# test.net
KiCad netlist of a schematic drawn in EAGLE
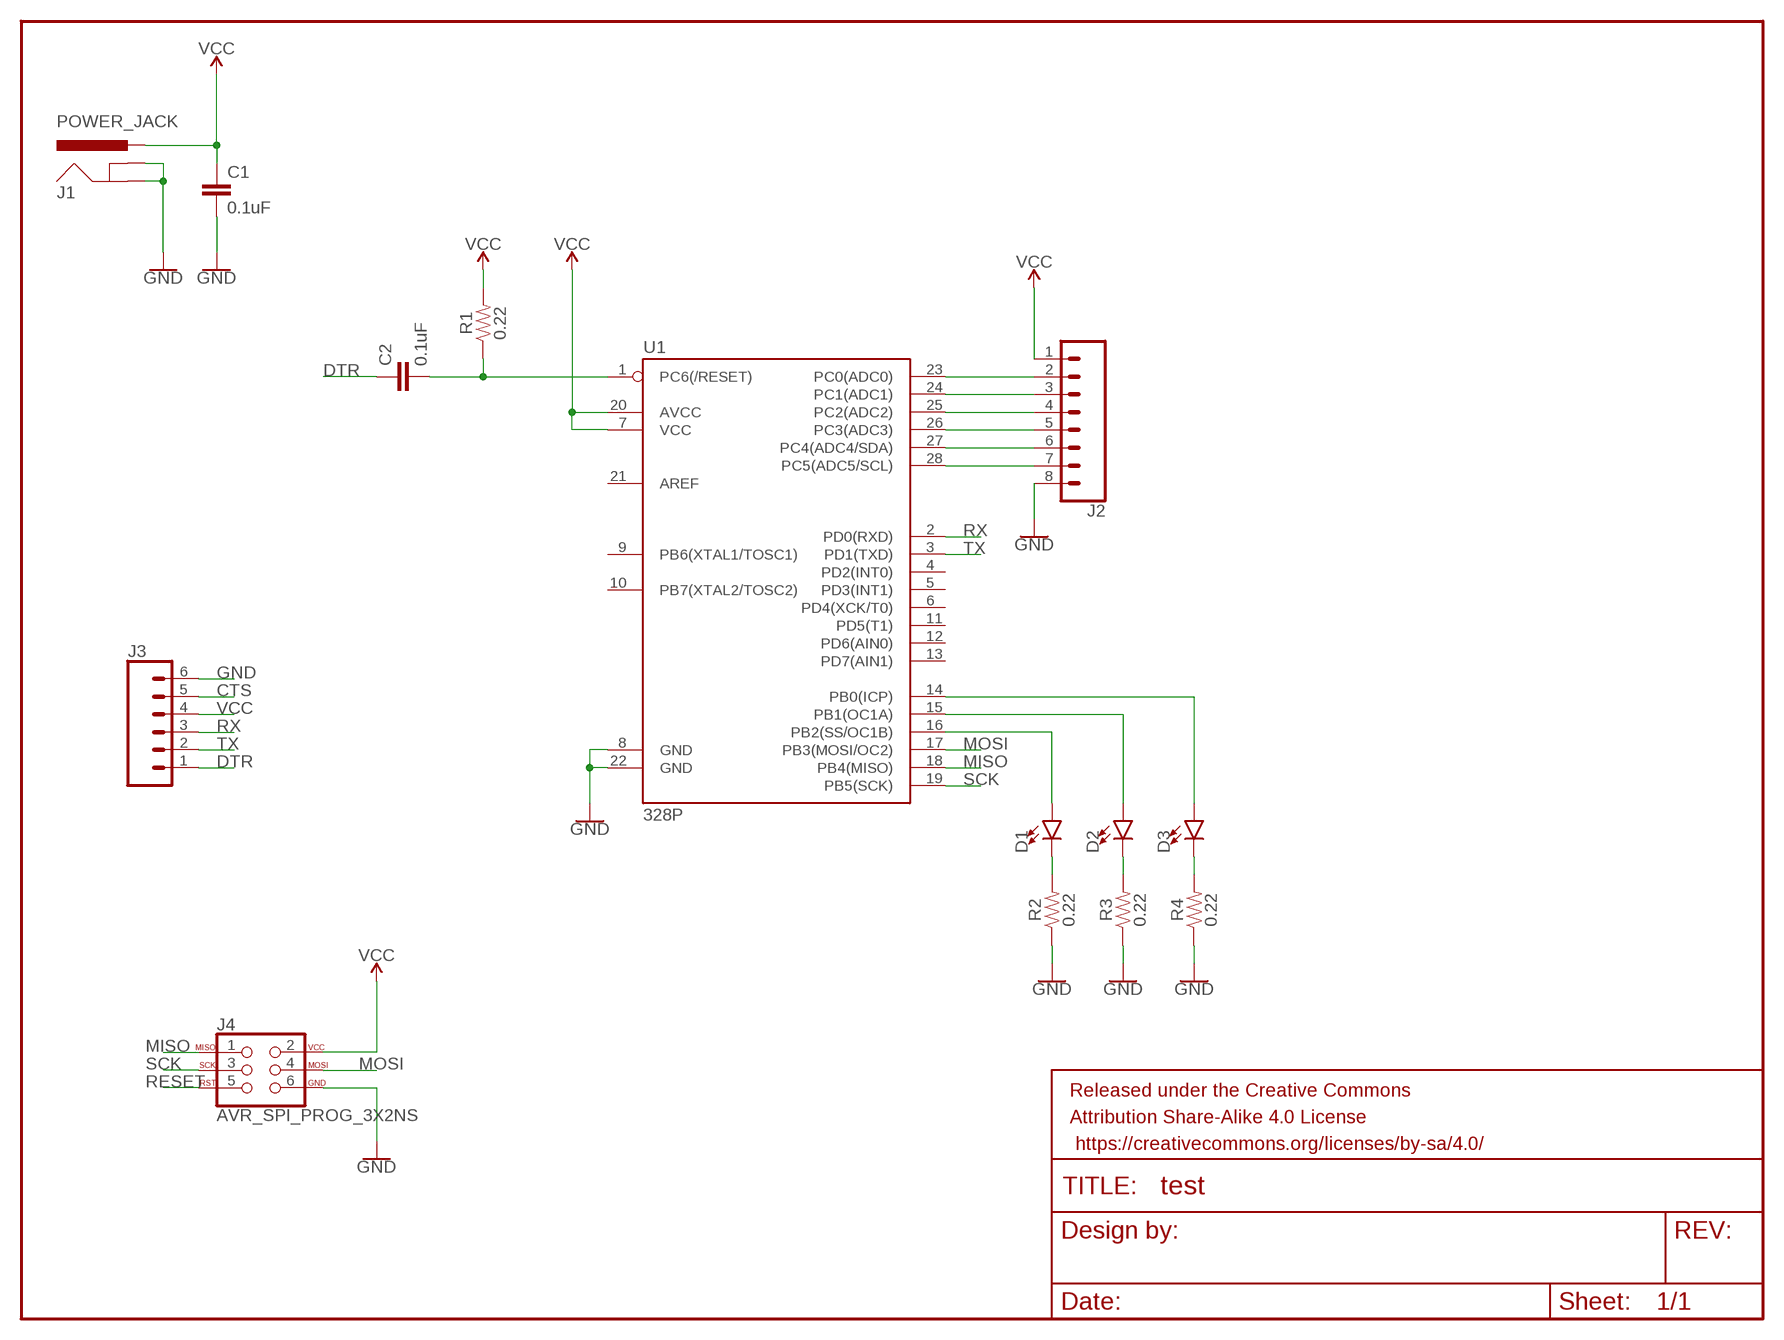
[diagram p0: schematic, sheet 1]

(export (version "E")
  (design (tool "Eeschema 10.0.6"))
  (components
    (comp (ref "C1")
      (value "0.1uF")
      (footprint "eagle-import:CAP-PTH-SMALL-KIT")
      (libsource (lib "eagle-import") (part "0.1UF-KIT-EZ-50V-20%"))
    )
    (comp (ref "C2")
      (value "0.1uF")
      (footprint "eagle-import:CAP-PTH-SMALL-KIT")
      (libsource (lib "eagle-import") (part "0.1UF-KIT-EZ-50V-20%"))
    )
    (comp (ref "D1")
      (value "LED5MM")
      (footprint "eagle-import:LED_5MM")
      (libsource (lib "eagle-import") (part "LED5MM"))
    )
    (comp (ref "D2")
      (value "LED5MM")
      (footprint "eagle-import:LED_5MM")
      (libsource (lib "eagle-import") (part "LED5MM"))
    )
    (comp (ref "D3")
      (value "LED5MM")
      (footprint "eagle-import:LED_5MM")
      (libsource (lib "eagle-import") (part "LED5MM"))
    )
    (comp (ref "FRAME1")
      (value "FRAME-LETTER")
      (footprint "eagle-import:CREATIVE_COMMONS")
      (libsource (lib "eagle-import") (part "FRAME-LETTER"))
    )
    (comp (ref "J1")
      (value "POWER_JACK")
      (footprint "eagle-import:POWER_JACK_PTH")
      (libsource (lib "eagle-import") (part "POWER_JACK"))
    )
    (comp (ref "J2")
      (value "CONN_08\"")
      (footprint "eagle-import:1X08")
      (libsource (lib "eagle-import") (part "CONN_08{dblquote}"))
    )
    (comp (ref "J3")
      (value "CONN_06LONGPADS")
      (footprint "eagle-import:1X06_LONGPADS")
      (libsource (lib "eagle-import") (part "CONN_06LONGPADS"))
    )
    (comp (ref "J4")
      (value "AVR_SPI_PROG_3X2NS")
      (footprint "eagle-import:2X3-NS")
      (libsource (lib "eagle-import") (part "AVR_SPI_PROG_3X2NS"))
    )
    (comp (ref "R1")
      (value "0.22")
      (footprint "eagle-import:0805")
      (libsource (lib "eagle-import") (part "0.22OHM-0805-1/4W-1%"))
    )
    (comp (ref "R2")
      (value "0.22")
      (footprint "eagle-import:0805")
      (libsource (lib "eagle-import") (part "0.22OHM-0805-1/4W-1%"))
    )
    (comp (ref "R3")
      (value "0.22")
      (footprint "eagle-import:0805")
      (libsource (lib "eagle-import") (part "0.22OHM-0805-1/4W-1%"))
    )
    (comp (ref "R4")
      (value "0.22")
      (footprint "eagle-import:0805")
      (libsource (lib "eagle-import") (part "0.22OHM-0805-1/4W-1%"))
    )
    (comp (ref "U1")
      (value "328P")
      (footprint "eagle-import:DIP28")
      (libsource (lib "eagle-import") (part "ATMEGA328P_PDIP"))
    )
  )
  (nets
    (net (code "1") (name "/CTS") (class "Default")
      (node (ref "J3") (pin "5") (pinfunction "5_5") (pintype "passive"))
    )
    (net (code "2") (name "/DTR") (class "Default")
      (node (ref "C2") (pin "1") (pinfunction "1_1") (pintype "passive"))
      (node (ref "J3") (pin "1") (pinfunction "1_1") (pintype "passive"))
    )
    (net (code "3") (name "/MISO") (class "Default")
      (node (ref "J4") (pin "1") (pinfunction "1_1") (pintype "passive"))
      (node (ref "U1") (pin "18") (pinfunction "PB4(MISO)_18") (pintype "bidirectional"))
    )
    (net (code "4") (name "/MOSI") (class "Default")
      (node (ref "J4") (pin "4") (pinfunction "4_4") (pintype "passive"))
      (node (ref "U1") (pin "17") (pinfunction "PB3(MOSI/OC2)_17") (pintype "bidirectional"))
    )
    (net (code "5") (name "/RESET") (class "Default")
      (node (ref "C2") (pin "2") (pinfunction "2_2") (pintype "passive"))
      (node (ref "J4") (pin "5") (pinfunction "5_5") (pintype "passive"))
      (node (ref "R1") (pin "1") (pinfunction "1_1") (pintype "passive"))
      (node (ref "U1") (pin "1") (pinfunction "PC6(/RESET)_1") (pintype "bidirectional"))
    )
    (net (code "6") (name "/RX") (class "Default")
      (node (ref "J3") (pin "3") (pinfunction "3_3") (pintype "passive"))
      (node (ref "U1") (pin "2") (pinfunction "PD0(RXD)_2") (pintype "bidirectional"))
    )
    (net (code "7") (name "/SCK") (class "Default")
      (node (ref "J4") (pin "3") (pinfunction "3_3") (pintype "passive"))
      (node (ref "U1") (pin "19") (pinfunction "PB5(SCK)_19") (pintype "bidirectional"))
    )
    (net (code "8") (name "/TX") (class "Default")
      (node (ref "J3") (pin "2") (pinfunction "2_2") (pintype "passive"))
      (node (ref "U1") (pin "3") (pinfunction "PD1(TXD)_3") (pintype "bidirectional"))
    )
    (net (code "9") (name "GND") (class "Default")
      (node (ref "C1") (pin "2") (pinfunction "2_2") (pintype "passive"))
      (node (ref "J1") (pin "GND") (pinfunction "GND_GND") (pintype "bidirectional"))
      (node (ref "J1") (pin "GNDBREAK") (pinfunction "GNDBREAK_GNDBREAK") (pintype "bidirectional"))
      (node (ref "J2") (pin "8") (pinfunction "8_8") (pintype "passive"))
      (node (ref "J3") (pin "6") (pinfunction "6_6") (pintype "passive"))
      (node (ref "J4") (pin "6") (pinfunction "6_6") (pintype "passive"))
      (node (ref "R2") (pin "1") (pinfunction "1_1") (pintype "passive"))
      (node (ref "R3") (pin "1") (pinfunction "1_1") (pintype "passive"))
      (node (ref "R4") (pin "1") (pinfunction "1_1") (pintype "passive"))
      (node (ref "U1") (pin "22") (pinfunction "GND_22") (pintype "bidirectional"))
      (node (ref "U1") (pin "8") (pinfunction "GND_8") (pintype "bidirectional"))
    )
    (net (code "10") (name "Net-(D1-C)") (class "Default")
      (node (ref "D1") (pin "K") (pinfunction "C_K") (pintype "passive"))
      (node (ref "R2") (pin "2") (pinfunction "2_2") (pintype "passive"))
    )
    (net (code "11") (name "Net-(D2-C)") (class "Default")
      (node (ref "D2") (pin "K") (pinfunction "C_K") (pintype "passive"))
      (node (ref "R3") (pin "2") (pinfunction "2_2") (pintype "passive"))
    )
    (net (code "12") (name "Net-(D3-C)") (class "Default")
      (node (ref "D3") (pin "K") (pinfunction "C_K") (pintype "passive"))
      (node (ref "R4") (pin "2") (pinfunction "2_2") (pintype "passive"))
    )
    (net (code "13") (name "Net-(U1-PB0(ICP))") (class "Default")
      (node (ref "D3") (pin "A") (pinfunction "A_A") (pintype "passive"))
      (node (ref "U1") (pin "14") (pinfunction "PB0(ICP)_14") (pintype "bidirectional"))
    )
    (net (code "14") (name "Net-(U1-PB1(OC1A))") (class "Default")
      (node (ref "D2") (pin "A") (pinfunction "A_A") (pintype "passive"))
      (node (ref "U1") (pin "15") (pinfunction "PB1(OC1A)_15") (pintype "bidirectional"))
    )
    (net (code "15") (name "Net-(U1-PB2(SS{slash}OC1B))") (class "Default")
      (node (ref "D1") (pin "A") (pinfunction "A_A") (pintype "passive"))
      (node (ref "U1") (pin "16") (pinfunction "PB2(SS/OC1B)_16") (pintype "bidirectional"))
    )
    (net (code "16") (name "Net-(U1-PC0(ADC0))") (class "Default")
      (node (ref "J2") (pin "2") (pinfunction "2_2") (pintype "passive"))
      (node (ref "U1") (pin "23") (pinfunction "PC0(ADC0)_23") (pintype "bidirectional"))
    )
    (net (code "17") (name "Net-(U1-PC1(ADC1))") (class "Default")
      (node (ref "J2") (pin "3") (pinfunction "3_3") (pintype "passive"))
      (node (ref "U1") (pin "24") (pinfunction "PC1(ADC1)_24") (pintype "bidirectional"))
    )
    (net (code "18") (name "Net-(U1-PC2(ADC2))") (class "Default")
      (node (ref "J2") (pin "4") (pinfunction "4_4") (pintype "passive"))
      (node (ref "U1") (pin "25") (pinfunction "PC2(ADC2)_25") (pintype "bidirectional"))
    )
    (net (code "19") (name "Net-(U1-PC3(ADC3))") (class "Default")
      (node (ref "J2") (pin "5") (pinfunction "5_5") (pintype "passive"))
      (node (ref "U1") (pin "26") (pinfunction "PC3(ADC3)_26") (pintype "bidirectional"))
    )
    (net (code "20") (name "Net-(U1-PC4(ADC4{slash}SDA))") (class "Default")
      (node (ref "J2") (pin "6") (pinfunction "6_6") (pintype "passive"))
      (node (ref "U1") (pin "27") (pinfunction "PC4(ADC4/SDA)_27") (pintype "bidirectional"))
    )
    (net (code "21") (name "Net-(U1-PC5(ADC5{slash}SCL))") (class "Default")
      (node (ref "J2") (pin "7") (pinfunction "7_7") (pintype "passive"))
      (node (ref "U1") (pin "28") (pinfunction "PC5(ADC5/SCL)_28") (pintype "bidirectional"))
    )
    (net (code "22") (name "VCC") (class "Default")
      (node (ref "C1") (pin "1") (pinfunction "1_1") (pintype "passive"))
      (node (ref "J1") (pin "PWR") (pinfunction "PWR_PWR") (pintype "bidirectional"))
      (node (ref "J2") (pin "1") (pinfunction "1_1") (pintype "passive"))
      (node (ref "J3") (pin "4") (pinfunction "4_4") (pintype "passive"))
      (node (ref "J4") (pin "2") (pinfunction "2_2") (pintype "passive"))
      (node (ref "R1") (pin "2") (pinfunction "2_2") (pintype "passive"))
      (node (ref "U1") (pin "20") (pinfunction "AVCC_20") (pintype "bidirectional"))
      (node (ref "U1") (pin "7") (pinfunction "VCC_7") (pintype "bidirectional"))
    )
    (net (code "23") (name "unconnected-(U1-AREF-Pad21)") (class "Default")
      (node (ref "U1") (pin "21") (pinfunction "AREF_21") (pintype "bidirectional"))
    )
    (net (code "24") (name "unconnected-(U1-PB6(XTAL1{slash}TOSC1)-Pad9)") (class "Default")
      (node (ref "U1") (pin "9") (pinfunction "PB6(XTAL1/TOSC1)_9") (pintype "bidirectional"))
    )
    (net (code "25") (name "unconnected-(U1-PB7(XTAL2{slash}TOSC2)-Pad10)") (class "Default")
      (node (ref "U1") (pin "10") (pinfunction "PB7(XTAL2/TOSC2)_10") (pintype "bidirectional"))
    )
    (net (code "26") (name "unconnected-(U1-PD2(INT0)-Pad4)") (class "Default")
      (node (ref "U1") (pin "4") (pinfunction "PD2(INT0)_4") (pintype "bidirectional"))
    )
    (net (code "27") (name "unconnected-(U1-PD3(INT1)-Pad5)") (class "Default")
      (node (ref "U1") (pin "5") (pinfunction "PD3(INT1)_5") (pintype "bidirectional"))
    )
    (net (code "28") (name "unconnected-(U1-PD4(XCK{slash}T0)-Pad6)") (class "Default")
      (node (ref "U1") (pin "6") (pinfunction "PD4(XCK/T0)_6") (pintype "bidirectional"))
    )
    (net (code "29") (name "unconnected-(U1-PD5(T1)-Pad11)") (class "Default")
      (node (ref "U1") (pin "11") (pinfunction "PD5(T1)_11") (pintype "bidirectional"))
    )
    (net (code "30") (name "unconnected-(U1-PD6(AIN0)-Pad12)") (class "Default")
      (node (ref "U1") (pin "12") (pinfunction "PD6(AIN0)_12") (pintype "bidirectional"))
    )
    (net (code "31") (name "unconnected-(U1-PD7(AIN1)-Pad13)") (class "Default")
      (node (ref "U1") (pin "13") (pinfunction "PD7(AIN1)_13") (pintype "bidirectional"))
    )
  )
)
